# cc2652r_v2_rs.net
KiCad netlist of a schematic drawn in EAGLE
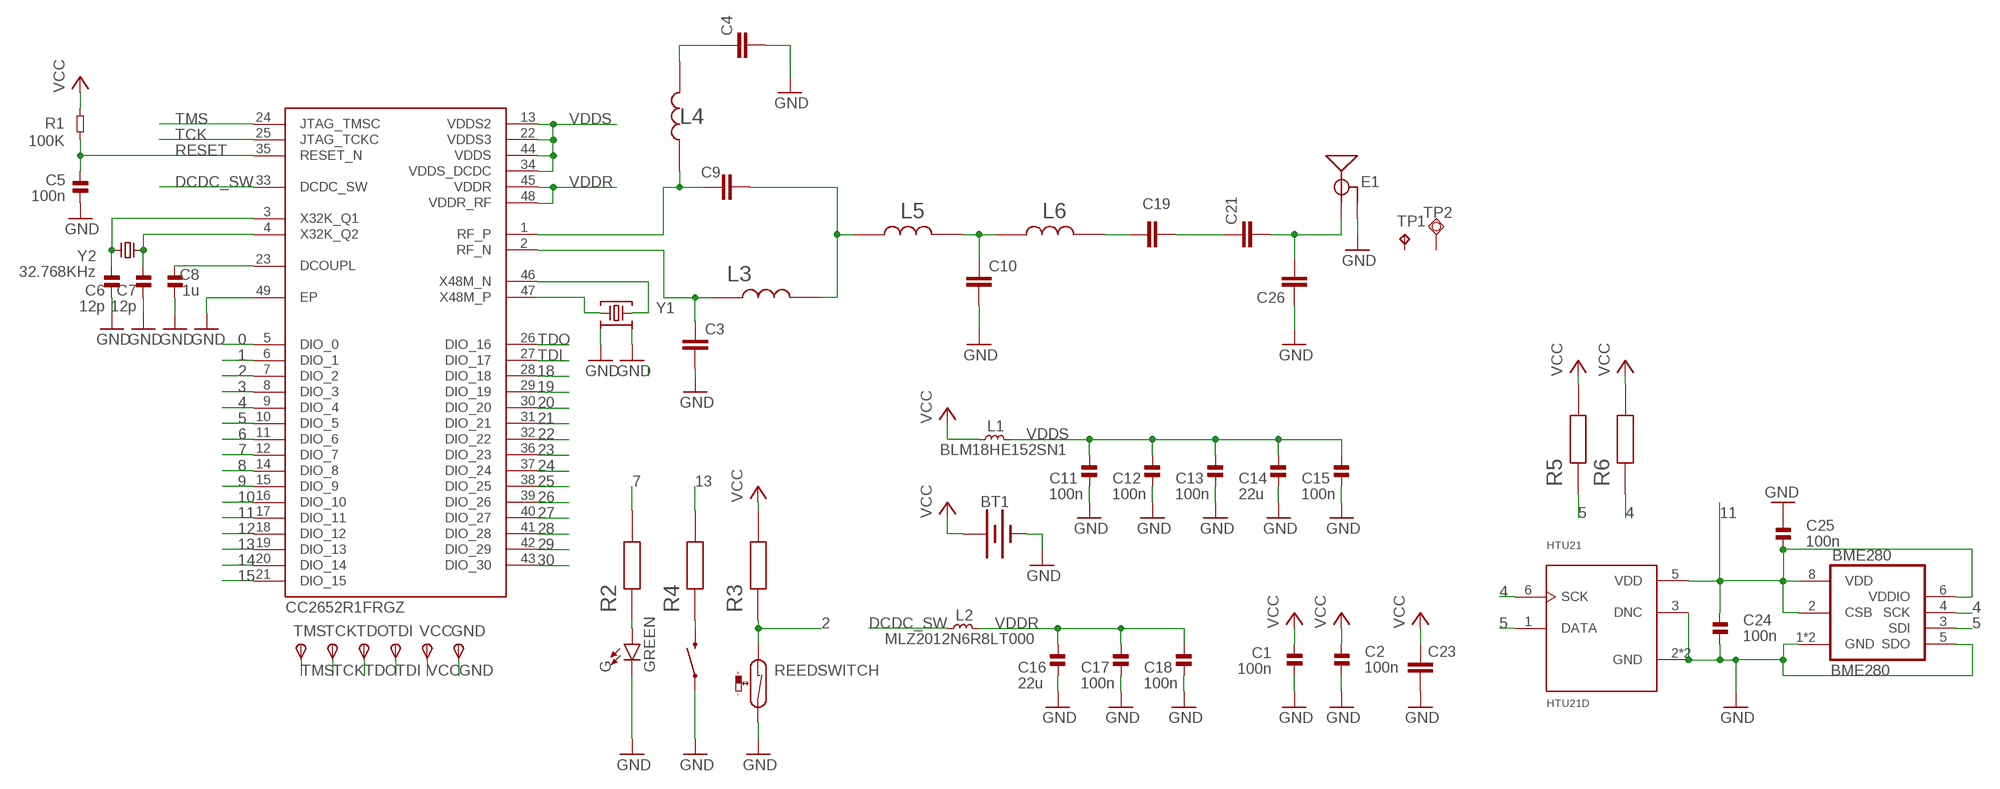
[diagram p0: schematic, sheet 1]

(export (version "E")
  (design (tool "Eeschema 10.0.6"))
  (components
    (comp (ref "BME280")
      (value "BME280")
      (footprint "eagle-import:BME280")
      (libsource (lib "eagle-import") (part "BME280"))
    )
    (comp (ref "BT1")
      (value "BATTERY-20MM_SMD")
      (footprint "eagle-import:BATTCON_20MM")
      (libsource (lib "eagle-import") (part "BATTERY-20MM_SMD"))
    )
    (comp (ref "C1")
      (value "100n")
      (footprint "eagle-import:_PKG_C_0402")
      (libsource (lib "eagle-import") (part "CAP-0402"))
    )
    (comp (ref "C2")
      (value "100n")
      (footprint "eagle-import:_PKG_C_0402")
      (libsource (lib "eagle-import") (part "CAP-0402"))
    )
    (comp (ref "C3")
      (value "CAP0402")
      (footprint "eagle-import:CAPC1005X40N")
      (fields (field (name "MF") "Yageo") (field (name "MP") "RC0402FR-073M6L"))
      (libsource (lib "eagle-import") (part "CAP0402"))
    )
    (comp (ref "C4")
      (value "12pF")
      (footprint "eagle-import:CAPC1005X40N")
      (fields (field (name "MF") "Yageo") (field (name "MP") "RC0402FR-073M6L"))
      (libsource (lib "eagle-import") (part "CAP0402"))
    )
    (comp (ref "C5")
      (value "100n")
      (footprint "eagle-import:_PKG_C_0402")
      (libsource (lib "eagle-import") (part "CAP-0402"))
    )
    (comp (ref "C6")
      (value "12p")
      (footprint "eagle-import:_PKG_C_0402")
      (libsource (lib "eagle-import") (part "CAP-0402"))
    )
    (comp (ref "C7")
      (value "12p")
      (footprint "eagle-import:_PKG_C_0402")
      (libsource (lib "eagle-import") (part "CAP-0402"))
    )
    (comp (ref "C8")
      (value "1u")
      (footprint "eagle-import:_PKG_C_0402")
      (libsource (lib "eagle-import") (part "CAP-0402"))
    )
    (comp (ref "C9")
      (value "1pF")
      (footprint "eagle-import:CAPC1005X40N")
      (fields (field (name "MF") "Yageo") (field (name "MP") "RC0402FR-073M6L"))
      (libsource (lib "eagle-import") (part "CAP0402"))
    )
    (comp (ref "C10")
      (value "1pF")
      (footprint "eagle-import:CAPC1005X40N")
      (fields (field (name "MF") "Yageo") (field (name "MP") "RC0402FR-073M6L"))
      (libsource (lib "eagle-import") (part "CAP0402"))
    )
    (comp (ref "C11")
      (value "100n")
      (footprint "eagle-import:_PKG_C_0402")
      (libsource (lib "eagle-import") (part "CAP-0402"))
    )
    (comp (ref "C12")
      (value "100n")
      (footprint "eagle-import:_PKG_C_0402")
      (libsource (lib "eagle-import") (part "CAP-0402"))
    )
    (comp (ref "C13")
      (value "100n")
      (footprint "eagle-import:_PKG_C_0402")
      (libsource (lib "eagle-import") (part "CAP-0402"))
    )
    (comp (ref "C14")
      (value "22u")
      (footprint "eagle-import:_PKG_C_0805")
      (libsource (lib "eagle-import") (part "CAP-0805"))
    )
    (comp (ref "C15")
      (value "100n")
      (footprint "eagle-import:_PKG_C_0402")
      (libsource (lib "eagle-import") (part "CAP-0402"))
    )
    (comp (ref "C16")
      (value "22u")
      (footprint "eagle-import:_PKG_C_0805")
      (libsource (lib "eagle-import") (part "CAP-0805"))
    )
    (comp (ref "C17")
      (value "100n")
      (footprint "eagle-import:_PKG_C_0402")
      (libsource (lib "eagle-import") (part "CAP-0402"))
    )
    (comp (ref "C18")
      (value "100n")
      (footprint "eagle-import:_PKG_C_0402")
      (libsource (lib "eagle-import") (part "CAP-0402"))
    )
    (comp (ref "C19")
      (value "12pF")
      (footprint "eagle-import:CAPC1005X40N")
      (fields (field (name "MF") "Yageo") (field (name "MP") "RC0402FR-073M6L"))
      (libsource (lib "eagle-import") (part "CAP0402"))
    )
    (comp (ref "C21")
      (value "1.8pF")
      (footprint "eagle-import:CAPC1005X40N")
      (fields (field (name "MF") "Yageo") (field (name "MP") "RC0402FR-073M6L"))
      (libsource (lib "eagle-import") (part "CAP0402"))
    )
    (comp (ref "C23")
      (value "C_TANTALUM-2917(7343-METRIC)")
      (footprint "eagle-import:CAPM7343X310")
      (libsource (lib "eagle-import") (part "CTANTALUM-2917(7343-METRIC)_"))
    )
    (comp (ref "C24")
      (value "100n")
      (footprint "eagle-import:_PKG_C_0402")
      (libsource (lib "eagle-import") (part "CAP-0402"))
    )
    (comp (ref "C25")
      (value "100n")
      (footprint "eagle-import:_PKG_C_0402")
      (libsource (lib "eagle-import") (part "CAP-0402"))
    )
    (comp (ref "C26")
      (value "CAP0402")
      (footprint "eagle-import:CAPC1005X40N")
      (fields (field (name "MF") "Yageo") (field (name "MP") "RC0402FR-073M6L"))
      (libsource (lib "eagle-import") (part "CAP0402"))
    )
    (comp (ref "E1")
      (value "ANTENNA-GROUNDEDTRACE-15.2MM")
      (footprint "eagle-import:TRACE_ANTENNA_2.4GHZ_15.2MM")
      (libsource (lib "eagle-import") (part "ANTENNA-GROUNDEDTRACE-15.2MM"))
    )
    (comp (ref "G")
      (value "GREEN")
      (footprint "eagle-import:LED-0603")
      (libsource (lib "eagle-import") (part "LED-GREEN0603"))
    )
    (comp (ref "GND")
      (value "TPSTP11R")
      (footprint "eagle-import:TP11R")
      (libsource (lib "eagle-import") (part "TPSTP11R"))
    )
    (comp (ref "HTU21")
      (value "HTU21D")
      (footprint "eagle-import:QFN100P300X300X100-7N")
      (fields (field (name "COMMENT") "CAT-HSC0004") (field (name "MF") "TE Connectivity"))
      (libsource (lib "eagle-import") (part "HTU21D"))
    )
    (comp (ref "IC3")
      (value "CC2652R1FRGZ")
      (footprint "eagle-import:QFN50P700X700X100-49N")
      (fields
        (field (name "ARROW_PART_NUMBER") "CC2652R1FRGZT")
        (field (name "MOUSER_PART_NUMBER") "595-CC2652R1FRGZT")
      )
      (libsource (lib "eagle-import") (part "CC2652R1FRGZT"))
    )
    (comp (ref "L1")
      (value "BLM18HE152SN1")
      (footprint "eagle-import:_PKG_L_0603")
      (libsource (lib "eagle-import") (part "INDUCTOR-0603"))
    )
    (comp (ref "L2")
      (value "MLZ2012N6R8LT000")
      (footprint "eagle-import:_PKG_C_0805")
      (libsource (lib "eagle-import") (part "INDUCTOR-0805"))
    )
    (comp (ref "L3")
      (value "2.4nH")
      (footprint "eagle-import:INDC1005X40N")
      (fields (field (name "MF") "Yageo") (field (name "MP") "RC0402FR-073M6L"))
      (libsource (lib "eagle-import") (part "IND0402IND0402"))
    )
    (comp (ref "L4")
      (value "2.4nH")
      (footprint "eagle-import:INDC1005X40N")
      (fields (field (name "MF") "Yageo") (field (name "MP") "RC0402FR-073M6L"))
      (libsource (lib "eagle-import") (part "IND0402IND0402"))
    )
    (comp (ref "L5")
      (value "2nH")
      (footprint "eagle-import:INDC1005X40N")
      (fields (field (name "MF") "Yageo") (field (name "MP") "RC0402FR-073M6L"))
      (libsource (lib "eagle-import") (part "IND0402IND0402"))
    )
    (comp (ref "L6")
      (value "2nH")
      (footprint "eagle-import:INDC1005X40N")
      (fields (field (name "MF") "Yageo") (field (name "MP") "RC0402FR-073M6L"))
      (libsource (lib "eagle-import") (part "IND0402IND0402"))
    )
    (comp (ref "R1")
      (value "100K")
      (footprint "eagle-import:_PKG_C_0402")
      (libsource (lib "eagle-import") (part "RES-0402"))
    )
    (comp (ref "R2")
      (value "2.2k")
      (footprint "eagle-import:RESC1005X40N")
      (fields (field (name "MF") "Yageo") (field (name "MP") "RC0402FR-073M6L"))
      (libsource (lib "eagle-import") (part "RES0402"))
    )
    (comp (ref "R3")
      (value "510k")
      (footprint "eagle-import:RESC1005X40N")
      (fields (field (name "MF") "Yageo") (field (name "MP") "RC0402FR-073M6L"))
      (libsource (lib "eagle-import") (part "RES0402"))
    )
    (comp (ref "R4")
      (value "100Ohm")
      (footprint "eagle-import:RESC1005X40N")
      (fields (field (name "MF") "Yageo") (field (name "MP") "RC0402FR-073M6L"))
      (libsource (lib "eagle-import") (part "RES0402"))
    )
    (comp (ref "R5")
      (value "10k")
      (footprint "eagle-import:RESC1005X40N")
      (fields (field (name "MF") "Yageo") (field (name "MP") "RC0402FR-073M6L"))
      (libsource (lib "eagle-import") (part "RES0402"))
    )
    (comp (ref "R6")
      (value "10k")
      (footprint "eagle-import:RESC1005X40N")
      (fields (field (name "MF") "Yageo") (field (name "MP") "RC0402FR-073M6L"))
      (libsource (lib "eagle-import") (part "RES0402"))
    )
    (comp (ref "REEDSWITCH")
      (value "REED-SWITCH-MK6-5-B")
      (footprint "eagle-import:MK6-5")
      (fields (field (name "MF") "MEDER") (field (name "MPN") "MK6-5-B"))
      (libsource (lib "eagle-import") (part "REED-SWITCH-MK6-5-B"))
    )
    (comp (ref "SW1")
      (value "MOMENTARY-SWITCH-SPST-SMD-4.6X2.8MM")
      (footprint "eagle-import:TACTILE_SWITCH_SMD_4.6X2.8MM")
      (libsource (lib "eagle-import") (part "MOMENTARY-SWITCH-SPST-SMD-4.6X2.8MM"))
    )
    (comp (ref "TCK")
      (value "TPSTP11R")
      (footprint "eagle-import:TP11R")
      (libsource (lib "eagle-import") (part "TPSTP11R"))
    )
    (comp (ref "TDI")
      (value "TPSTP11R")
      (footprint "eagle-import:TP11R")
      (libsource (lib "eagle-import") (part "TPSTP11R"))
    )
    (comp (ref "TDO")
      (value "TPSTP11R")
      (footprint "eagle-import:TP11R")
      (libsource (lib "eagle-import") (part "TPSTP11R"))
    )
    (comp (ref "TMS")
      (value "TPSTP11R")
      (footprint "eagle-import:TP11R")
      (libsource (lib "eagle-import") (part "TPSTP11R"))
    )
    (comp (ref "TP1")
      (value "TPTP06SQ")
      (footprint "eagle-import:TP05SQ")
      (libsource (lib "eagle-import") (part "TPTP06SQ"))
    )
    (comp (ref "TP2")
      (value "TPSQTP15SQ")
      (footprint "eagle-import:TP15SQ")
      (libsource (lib "eagle-import") (part "TPSQTP15SQ"))
    )
    (comp (ref "VCC")
      (value "TPSTP11R")
      (footprint "eagle-import:TP11R")
      (libsource (lib "eagle-import") (part "TPSTP11R"))
    )
    (comp (ref "Y1")
      (value "Q22FA12800150")
      (footprint "eagle-import:XTAL-4P-2016")
      (fields (field (name "DIGIKEY_PART") "1253-2042-1-ND") (field (name "MFG_PART") "CX2016DB48000C0FPLC1"))
      (libsource (lib "eagle-import") (part "48.000MHZ_CX2016DB48000C0FPLC1"))
    )
    (comp (ref "Y2")
      (value "32.768KHz")
      (footprint "eagle-import:XTAL-2P-3215")
      (fields (field (name "LCSC_PART") "C32346") (field (name "MFG_PART") "Q13FC1350000400"))
      (libsource (lib "eagle-import") (part "32.768KHZ_Q13FC1350000400"))
    )
  )
  (nets
    (net (code "1") (name "/0") (class "Default")
      (node (ref "IC3") (pin "5") (pinfunction "DIO_0_5") (pintype "bidirectional"))
    )
    (net (code "2") (name "/1") (class "Default")
      (node (ref "IC3") (pin "6") (pinfunction "DIO_1_6") (pintype "bidirectional"))
    )
    (net (code "3") (name "/2") (class "Default")
      (node (ref "IC3") (pin "7") (pinfunction "DIO_2_7") (pintype "bidirectional"))
      (node (ref "R3") (pin "1") (pinfunction "1_1") (pintype "passive"))
      (node (ref "REEDSWITCH") (pin "1") (pinfunction "1_1") (pintype "passive"))
    )
    (net (code "4") (name "/3") (class "Default")
      (node (ref "IC3") (pin "8") (pinfunction "DIO_3_8") (pintype "bidirectional"))
    )
    (net (code "5") (name "/4") (class "Default")
      (node (ref "BME280") (pin "4") (pinfunction "SCK_4") (pintype "bidirectional"))
      (node (ref "HTU21") (pin "6") (pinfunction "SCK_6") (pintype "input"))
      (node (ref "IC3") (pin "9") (pinfunction "DIO_4_9") (pintype "bidirectional"))
      (node (ref "R6") (pin "1") (pinfunction "1_1") (pintype "passive"))
    )
    (net (code "6") (name "/5") (class "Default")
      (node (ref "BME280") (pin "3") (pinfunction "SDI_3") (pintype "bidirectional"))
      (node (ref "HTU21") (pin "1") (pinfunction "DATA_1") (pintype "bidirectional"))
      (node (ref "IC3") (pin "10") (pinfunction "DIO_5_10") (pintype "bidirectional"))
      (node (ref "R5") (pin "1") (pinfunction "1_1") (pintype "passive"))
    )
    (net (code "7") (name "/6") (class "Default")
      (node (ref "IC3") (pin "11") (pinfunction "DIO_6_11") (pintype "bidirectional"))
    )
    (net (code "8") (name "/7") (class "Default")
      (node (ref "IC3") (pin "12") (pinfunction "DIO_7_12") (pintype "bidirectional"))
      (node (ref "R2") (pin "2") (pinfunction "2_2") (pintype "passive"))
    )
    (net (code "9") (name "/8") (class "Default")
      (node (ref "IC3") (pin "14") (pinfunction "DIO_8_14") (pintype "bidirectional"))
    )
    (net (code "10") (name "/9") (class "Default")
      (node (ref "IC3") (pin "15") (pinfunction "DIO_9_15") (pintype "bidirectional"))
    )
    (net (code "11") (name "/10") (class "Default")
      (node (ref "IC3") (pin "16") (pinfunction "DIO_10_16") (pintype "bidirectional"))
    )
    (net (code "12") (name "/11") (class "Default")
      (node (ref "BME280") (pin "2") (pinfunction "CSB_2") (pintype "input"))
      (node (ref "BME280") (pin "6") (pinfunction "VDDIO_6") (pintype "power_in"))
      (node (ref "BME280") (pin "8") (pinfunction "VDD_8") (pintype "power_in"))
      (node (ref "C24") (pin "2") (pinfunction "2_2") (pintype "passive"))
      (node (ref "C25") (pin "1") (pinfunction "1_1") (pintype "passive"))
      (node (ref "HTU21") (pin "5") (pinfunction "VDD_5") (pintype "power_in"))
      (node (ref "IC3") (pin "17") (pinfunction "DIO_11_17") (pintype "bidirectional"))
    )
    (net (code "13") (name "/12") (class "Default")
      (node (ref "IC3") (pin "18") (pinfunction "DIO_12_18") (pintype "bidirectional"))
    )
    (net (code "14") (name "/13") (class "Default")
      (node (ref "IC3") (pin "19") (pinfunction "DIO_13_19") (pintype "bidirectional"))
      (node (ref "R4") (pin "2") (pinfunction "2_2") (pintype "passive"))
    )
    (net (code "15") (name "/14") (class "Default")
      (node (ref "IC3") (pin "20") (pinfunction "DIO_14_20") (pintype "bidirectional"))
    )
    (net (code "16") (name "/15") (class "Default")
      (node (ref "IC3") (pin "21") (pinfunction "DIO_15_21") (pintype "bidirectional"))
    )
    (net (code "17") (name "/18") (class "Default")
      (node (ref "IC3") (pin "28") (pinfunction "DIO_18_28") (pintype "bidirectional"))
    )
    (net (code "18") (name "/19") (class "Default")
      (node (ref "IC3") (pin "29") (pinfunction "DIO_19_29") (pintype "bidirectional"))
    )
    (net (code "19") (name "/20") (class "Default")
      (node (ref "IC3") (pin "30") (pinfunction "DIO_20_30") (pintype "bidirectional"))
    )
    (net (code "20") (name "/21") (class "Default")
      (node (ref "IC3") (pin "31") (pinfunction "DIO_21_31") (pintype "bidirectional"))
    )
    (net (code "21") (name "/22") (class "Default")
      (node (ref "IC3") (pin "32") (pinfunction "DIO_22_32") (pintype "bidirectional"))
    )
    (net (code "22") (name "/23") (class "Default")
      (node (ref "IC3") (pin "36") (pinfunction "DIO_23_36") (pintype "bidirectional"))
    )
    (net (code "23") (name "/24") (class "Default")
      (node (ref "IC3") (pin "37") (pinfunction "DIO_24_37") (pintype "bidirectional"))
    )
    (net (code "24") (name "/25") (class "Default")
      (node (ref "IC3") (pin "38") (pinfunction "DIO_25_38") (pintype "bidirectional"))
    )
    (net (code "25") (name "/26") (class "Default")
      (node (ref "IC3") (pin "39") (pinfunction "DIO_26_39") (pintype "bidirectional"))
    )
    (net (code "26") (name "/27") (class "Default")
      (node (ref "IC3") (pin "40") (pinfunction "DIO_27_40") (pintype "bidirectional"))
    )
    (net (code "27") (name "/28") (class "Default")
      (node (ref "IC3") (pin "41") (pinfunction "DIO_28_41") (pintype "bidirectional"))
    )
    (net (code "28") (name "/29") (class "Default")
      (node (ref "IC3") (pin "42") (pinfunction "DIO_29_42") (pintype "bidirectional"))
    )
    (net (code "29") (name "/30") (class "Default")
      (node (ref "IC3") (pin "43") (pinfunction "DIO_30_43") (pintype "bidirectional"))
    )
    (net (code "30") (name "/DCDC_SW") (class "Default")
      (node (ref "IC3") (pin "33") (pinfunction "DCDC_SW_33") (pintype "bidirectional"))
      (node (ref "L2") (pin "1") (pinfunction "1_1") (pintype "passive"))
    )
    (net (code "31") (name "/RESET") (class "Default")
      (node (ref "C5") (pin "2") (pinfunction "2_2") (pintype "passive"))
      (node (ref "IC3") (pin "35") (pinfunction "RESET_N_35") (pintype "bidirectional"))
      (node (ref "R1") (pin "1") (pinfunction "1_1") (pintype "passive"))
    )
    (net (code "32") (name "/TCK") (class "Default")
      (node (ref "IC3") (pin "25") (pinfunction "JTAG_TCKC_25") (pintype "bidirectional"))
      (node (ref "TCK") (pin "TP") (pinfunction "PP_TP") (pintype "input"))
    )
    (net (code "33") (name "/TDI") (class "Default")
      (node (ref "IC3") (pin "27") (pinfunction "DIO_17_27") (pintype "bidirectional"))
      (node (ref "TDI") (pin "TP") (pinfunction "PP_TP") (pintype "input"))
    )
    (net (code "34") (name "/TDO") (class "Default")
      (node (ref "IC3") (pin "26") (pinfunction "DIO_16_26") (pintype "bidirectional"))
      (node (ref "TDO") (pin "TP") (pinfunction "PP_TP") (pintype "input"))
    )
    (net (code "35") (name "/TMS") (class "Default")
      (node (ref "IC3") (pin "24") (pinfunction "JTAG_TMSC_24") (pintype "bidirectional"))
      (node (ref "TMS") (pin "TP") (pinfunction "PP_TP") (pintype "input"))
    )
    (net (code "36") (name "/VDDR") (class "Default")
      (node (ref "C16") (pin "1") (pinfunction "1_1") (pintype "passive"))
      (node (ref "C17") (pin "1") (pinfunction "1_1") (pintype "passive"))
      (node (ref "C18") (pin "1") (pinfunction "1_1") (pintype "passive"))
      (node (ref "IC3") (pin "45") (pinfunction "VDDR_45") (pintype "bidirectional"))
      (node (ref "IC3") (pin "48") (pinfunction "VDDR_RF_48") (pintype "bidirectional"))
      (node (ref "L2") (pin "2") (pinfunction "2_2") (pintype "passive"))
    )
    (net (code "37") (name "/VDDS") (class "Default")
      (node (ref "C11") (pin "1") (pinfunction "1_1") (pintype "passive"))
      (node (ref "C12") (pin "1") (pinfunction "1_1") (pintype "passive"))
      (node (ref "C13") (pin "1") (pinfunction "1_1") (pintype "passive"))
      (node (ref "C14") (pin "1") (pinfunction "1_1") (pintype "passive"))
      (node (ref "C15") (pin "1") (pinfunction "1_1") (pintype "passive"))
      (node (ref "IC3") (pin "13") (pinfunction "VDDS2_13") (pintype "bidirectional"))
      (node (ref "IC3") (pin "22") (pinfunction "VDDS3_22") (pintype "bidirectional"))
      (node (ref "IC3") (pin "34") (pinfunction "VDDS_DCDC_34") (pintype "bidirectional"))
      (node (ref "IC3") (pin "44") (pinfunction "VDDS_44") (pintype "bidirectional"))
      (node (ref "L1") (pin "2") (pinfunction "2_2") (pintype "passive"))
    )
    (net (code "38") (name "GND") (class "Default")
      (node (ref "BME280") (pin "1") (pinfunction "GND_1") (pintype "power_in"))
      (node (ref "BME280") (pin "5") (pinfunction "SDO_5") (pintype "input"))
      (node (ref "BME280") (pin "7") (pinfunction "GND_7") (pintype "power_in"))
      (node (ref "BT1") (pin "2") (pinfunction "-_2") (pintype "power_in"))
      (node (ref "C1") (pin "1") (pinfunction "1_1") (pintype "passive"))
      (node (ref "C10") (pin "2") (pinfunction "2_2") (pintype "passive"))
      (node (ref "C11") (pin "2") (pinfunction "2_2") (pintype "passive"))
      (node (ref "C12") (pin "2") (pinfunction "2_2") (pintype "passive"))
      (node (ref "C13") (pin "2") (pinfunction "2_2") (pintype "passive"))
      (node (ref "C14") (pin "2") (pinfunction "2_2") (pintype "passive"))
      (node (ref "C15") (pin "2") (pinfunction "2_2") (pintype "passive"))
      (node (ref "C16") (pin "2") (pinfunction "2_2") (pintype "passive"))
      (node (ref "C17") (pin "2") (pinfunction "2_2") (pintype "passive"))
      (node (ref "C18") (pin "2") (pinfunction "2_2") (pintype "passive"))
      (node (ref "C2") (pin "1") (pinfunction "1_1") (pintype "passive"))
      (node (ref "C23") (pin "2") (pinfunction "2_2") (pintype "passive"))
      (node (ref "C24") (pin "1") (pinfunction "1_1") (pintype "passive"))
      (node (ref "C25") (pin "2") (pinfunction "2_2") (pintype "passive"))
      (node (ref "C26") (pin "1") (pinfunction "1_1") (pintype "passive"))
      (node (ref "C3") (pin "2") (pinfunction "2_2") (pintype "passive"))
      (node (ref "C4") (pin "2") (pinfunction "2_2") (pintype "passive"))
      (node (ref "C5") (pin "1") (pinfunction "1_1") (pintype "passive"))
      (node (ref "C6") (pin "1") (pinfunction "1_1") (pintype "passive"))
      (node (ref "C7") (pin "1") (pinfunction "1_1") (pintype "passive"))
      (node (ref "C8") (pin "1") (pinfunction "1_1") (pintype "passive"))
      (node (ref "E1") (pin "GND") (pinfunction "GND_GND") (pintype "bidirectional"))
      (node (ref "G") (pin "C") (pinfunction "C_C") (pintype "passive"))
      (node (ref "GND") (pin "TP") (pinfunction "PP_TP") (pintype "input"))
      (node (ref "HTU21") (pin "2") (pinfunction "GND_2") (pintype "passive"))
      (node (ref "HTU21") (pin "3") (pinfunction "DNC_3") (pintype "bidirectional"))
      (node (ref "HTU21") (pin "PAD") (pinfunction "GND_PAD") (pintype "passive"))
      (node (ref "IC3") (pin "49") (pinfunction "EP_49") (pintype "bidirectional"))
      (node (ref "REEDSWITCH") (pin "2") (pinfunction "2_2") (pintype "passive"))
      (node (ref "SW1") (pin "1") (pinfunction "1_1") (pintype "passive"))
      (node (ref "SW1") (pin "2") (pinfunction "1_2") (pintype "passive"))
      (node (ref "Y1") (pin "2") (pinfunction "2_2") (pintype "bidirectional"))
      (node (ref "Y1") (pin "4") (pinfunction "4_4") (pintype "bidirectional"))
    )
    (net (code "39") (name "Net-(C4-Pad1)") (class "Default")
      (node (ref "C4") (pin "1") (pinfunction "1_1") (pintype "passive"))
      (node (ref "L4") (pin "2") (pinfunction "2_2") (pintype "passive"))
    )
    (net (code "40") (name "Net-(C9-Pad2)") (class "Default")
      (node (ref "C9") (pin "2") (pinfunction "2_2") (pintype "passive"))
      (node (ref "L3") (pin "2") (pinfunction "2_2") (pintype "passive"))
      (node (ref "L5") (pin "1") (pinfunction "1_1") (pintype "passive"))
    )
    (net (code "41") (name "Net-(C10-Pad1)") (class "Default")
      (node (ref "C10") (pin "1") (pinfunction "1_1") (pintype "passive"))
      (node (ref "L5") (pin "2") (pinfunction "2_2") (pintype "passive"))
      (node (ref "L6") (pin "1") (pinfunction "1_1") (pintype "passive"))
    )
    (net (code "42") (name "Net-(C19-Pad1)") (class "Default")
      (node (ref "C19") (pin "1") (pinfunction "1_1") (pintype "passive"))
      (node (ref "L6") (pin "2") (pinfunction "2_2") (pintype "passive"))
    )
    (net (code "43") (name "Net-(C19-Pad2)") (class "Default")
      (node (ref "C19") (pin "2") (pinfunction "2_2") (pintype "passive"))
      (node (ref "C21") (pin "1") (pinfunction "1_1") (pintype "passive"))
    )
    (net (code "44") (name "Net-(E1-SIGNAL)") (class "Default")
      (node (ref "C21") (pin "2") (pinfunction "2_2") (pintype "passive"))
      (node (ref "C26") (pin "2") (pinfunction "2_2") (pintype "passive"))
      (node (ref "E1") (pin "ANT") (pinfunction "SIGNAL_ANT") (pintype "bidirectional"))
    )
    (net (code "45") (name "Net-(G-PadA)") (class "Default")
      (node (ref "G") (pin "A") (pinfunction "A_A") (pintype "passive"))
      (node (ref "R2") (pin "1") (pinfunction "1_1") (pintype "passive"))
    )
    (net (code "46") (name "Net-(IC3-DCOUPL)") (class "Default")
      (node (ref "C8") (pin "2") (pinfunction "2_2") (pintype "passive"))
      (node (ref "IC3") (pin "23") (pinfunction "DCOUPL_23") (pintype "bidirectional"))
    )
    (net (code "47") (name "Net-(IC3-RF_N)") (class "Default")
      (node (ref "C3") (pin "1") (pinfunction "1_1") (pintype "passive"))
      (node (ref "IC3") (pin "2") (pinfunction "RF_N_2") (pintype "bidirectional"))
      (node (ref "L3") (pin "1") (pinfunction "1_1") (pintype "passive"))
    )
    (net (code "48") (name "Net-(IC3-RF_P)") (class "Default")
      (node (ref "C9") (pin "1") (pinfunction "1_1") (pintype "passive"))
      (node (ref "IC3") (pin "1") (pinfunction "RF_P_1") (pintype "bidirectional"))
      (node (ref "L4") (pin "1") (pinfunction "1_1") (pintype "passive"))
    )
    (net (code "49") (name "Net-(IC3-X32K_Q1)") (class "Default")
      (node (ref "C6") (pin "2") (pinfunction "2_2") (pintype "passive"))
      (node (ref "IC3") (pin "3") (pinfunction "X32K_Q1_3") (pintype "bidirectional"))
      (node (ref "Y2") (pin "1") (pinfunction "1_1") (pintype "passive"))
    )
    (net (code "50") (name "Net-(IC3-X32K_Q2)") (class "Default")
      (node (ref "C7") (pin "2") (pinfunction "2_2") (pintype "passive"))
      (node (ref "IC3") (pin "4") (pinfunction "X32K_Q2_4") (pintype "bidirectional"))
      (node (ref "Y2") (pin "2") (pinfunction "2_2") (pintype "passive"))
    )
    (net (code "51") (name "Net-(IC3-X48M_N)") (class "Default")
      (node (ref "IC3") (pin "46") (pinfunction "X48M_N_46") (pintype "bidirectional"))
      (node (ref "Y1") (pin "3") (pinfunction "3_3") (pintype "passive"))
    )
    (net (code "52") (name "Net-(IC3-X48M_P)") (class "Default")
      (node (ref "IC3") (pin "47") (pinfunction "X48M_P_47") (pintype "bidirectional"))
      (node (ref "Y1") (pin "1") (pinfunction "1_1") (pintype "passive"))
    )
    (net (code "53") (name "Net-(R4-Pad1)") (class "Default")
      (node (ref "R4") (pin "1") (pinfunction "1_1") (pintype "passive"))
      (node (ref "SW1") (pin "3") (pinfunction "2_3") (pintype "passive"))
      (node (ref "SW1") (pin "4") (pinfunction "2_4") (pintype "passive"))
    )
    (net (code "54") (name "VCC") (class "Default")
      (node (ref "BT1") (pin "1") (pinfunction "+_1") (pintype "power_in"))
      (node (ref "C1") (pin "2") (pinfunction "2_2") (pintype "passive"))
      (node (ref "C2") (pin "2") (pinfunction "2_2") (pintype "passive"))
      (node (ref "C23") (pin "1") (pinfunction "1_1") (pintype "passive"))
      (node (ref "L1") (pin "1") (pinfunction "1_1") (pintype "passive"))
      (node (ref "R1") (pin "2") (pinfunction "2_2") (pintype "passive"))
      (node (ref "R3") (pin "2") (pinfunction "2_2") (pintype "passive"))
      (node (ref "R5") (pin "2") (pinfunction "2_2") (pintype "passive"))
      (node (ref "R6") (pin "2") (pinfunction "2_2") (pintype "passive"))
      (node (ref "VCC") (pin "TP") (pinfunction "PP_TP") (pintype "input"))
    )
    (net (code "55") (name "unconnected-(TP1-PadTP)") (class "Default")
      (node (ref "TP1") (pin "TP") (pinfunction "TP_TP") (pintype "input"))
    )
    (net (code "56") (name "unconnected-(TP2-PadTP)") (class "Default")
      (node (ref "TP2") (pin "TP") (pinfunction "TP_TP") (pintype "input"))
    )
  )
)
